# io.net
KiCad netlist of a schematic drawn in Altium Designer
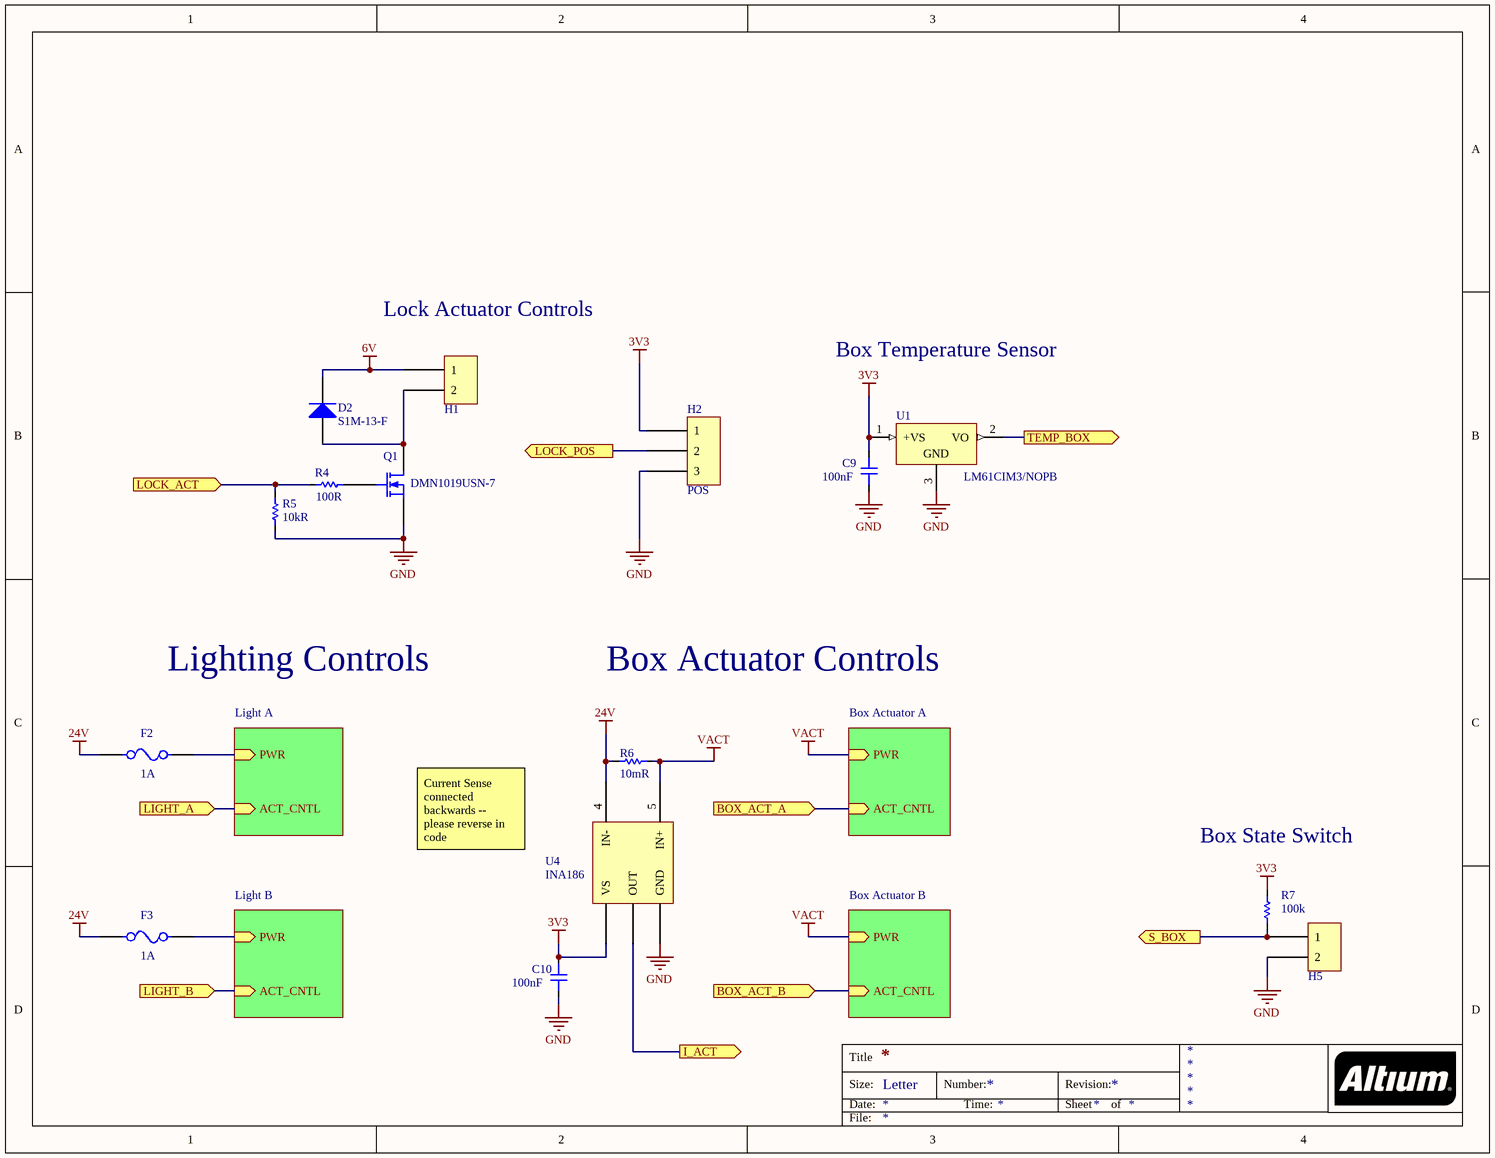
[diagram p0: io.schdoc]

(export (version "E")
  (design (tool "Eeschema 10.0.6"))
  (components
    (comp (ref "C9")
      (value "value")
      (footprint "CAP 0805 L")
      (fields
        (field (name "MANUFACTURER") "KEMET")
        (field (name "MANUFACTURER PART NUMBER") "C0805C104K3RACAUTO")
        (field (name "TOLERANCE") "10%")
        (field (name "CAPACITANCE") "100nF")
      )
      (libsource (lib "streetbot") (part "CAP 0805"))
    )
    (comp (ref "C10")
      (value "value")
      (footprint "CAP 0805 L")
      (fields
        (field (name "MANUFACTURER") "KEMET")
        (field (name "MANUFACTURER PART NUMBER") "C0805C104K3RACAUTO")
        (field (name "TOLERANCE") "10%")
        (field (name "CAPACITANCE") "100nF")
      )
      (libsource (lib "streetbot") (part "CAP 0805"))
    )
    (comp (ref "D2")
      (value "S1M-13-F")
      (footprint "SMA")
      (description "Default Diode")
      (libsource (lib "Miscellaneous Devices") (part "Diode"))
    )
    (comp (ref "F2")
      (value "0154001.DRT")
      (footprint "Littelfuse_0154_0")
      (description "LITTELFUSE - 0154001.DRT - FUSE, SMD, 1A, OMNI BLOCK, TIME DELAY")
      (fields (field (name "MANUFACTURER") "Littelfuse") (field (name "CURRENT RATING") "1A"))
      (libsource (lib "food_box") (part "0154005.DRT"))
    )
    (comp (ref "F3")
      (value "0154001.DRT")
      (footprint "Littelfuse_0154_0")
      (description "LITTELFUSE - 0154001.DRT - FUSE, SMD, 1A, OMNI BLOCK, TIME DELAY")
      (fields (field (name "MANUFACTURER") "Littelfuse") (field (name "CURRENT RATING") "1A"))
      (libsource (lib "food_box") (part "0154005.DRT"))
    )
    (comp (ref "H1")
      (value "MOLEX_43650_2")
      (footprint "MOLEX_43650_2")
      (fields (field (name "MANUFACTURER") "Molex") (field (name "MANUFACTURER PART NUMBER") "43650-0227"))
      (libsource (lib "food_box") (part "MOLEX_43650_2"))
    )
    (comp (ref "H2")
      (value "POS")
      (footprint "MOLEX_43650_3")
      (description "Stepper position potentiometer")
      (libsource (lib "food_box") (part "TERM_3P"))
    )
    (comp (ref "H5")
      (value "MOLEX_43650_2")
      (footprint "MOLEX_43650_2")
      (fields (field (name "MANUFACTURER") "Molex") (field (name "MANUFACTURER PART NUMBER") "43650-0227"))
      (libsource (lib "food_box") (part "MOLEX_43650_2"))
    )
    (comp (ref "Q1")
      (value "MOSFET-N")
      (footprint "SOT23-3")
      (description "MOSFET 12V N-Ch Enh FET 2426pF 27.3nC")
      (fields (field (name "MANUFACTURER") "Diodes") (field (name "MANUFACTURER PART NUMBER") "DMN1019USN-7"))
      (libsource (lib "Miscellaneous Devices") (part "MOSFET-N"))
    )
    (comp (ref "R4")
      (value "value")
      (footprint "RES 0603 L")
      (description "CRGCQ 0603 100R 5%")
      (fields
        (field (name "MANUFACTURER") "TE Connectivity")
        (field (name "MANUFACTURER PART NUMBER") "CRGCQ0603J100R")
        (field (name "RESISTANCE") "100R")
      )
      (libsource (lib "streetbot") (part "RES 0603"))
    )
    (comp (ref "R5")
      (value "value")
      (footprint "RES 0603 L")
      (description "TE CONNECTIVITY - CRGCQ0603J10K - RES, 10K, 5%, 0603, THICK FILM")
      (fields
        (field (name "MANUFACTURER") "TE Connectivity")
        (field (name "MANUFACTURER PART NUMBER") "CRGCQ0603J10K")
        (field (name "RESISTANCE") "10kR")
      )
      (libsource (lib "streetbot") (part "RES 0603"))
    )
    (comp (ref "R6")
      (value "10mR")
      (footprint "CAP 0805 L")
      (description "Resistor Thick Film 0.01Ohm 0.5% 0.5W 2-Pin 0805 T/R")
      (fields
        (field (name "MANUFACTURER") "Panasonic")
        (field (name "MANUFACTURER PART NUMBER") "ERJ-6CWDR010V")
      )
      (libsource (lib "streetbot") (part "RES 0603"))
    )
    (comp (ref "R7")
      (value "value")
      (footprint "RES 0603 L")
      (description "CRGCQ 0603 100K 5%")
      (fields
        (field (name "MANUFACTURER") "TE Connectivity")
        (field (name "MANUFACTURER PART NUMBER") "CRGCQ0603J100K")
        (field (name "RESISTANCE") "100k")
      )
      (libsource (lib "streetbot") (part "RES 0603"))
    )
    (comp (ref "U1")
      (value "LM61CIM3/NOPB")
      (footprint "DBZ0003A_L")
      (description "2.7V Temperature Sensor, 3-pin SOT-23, Pb-Free")
      (fields (field (name "MANUFACTURER") "Texas Instruments"))
      (libsource (lib "Altium Content Vault") (part "SEN-TEMP-LM34AH-3"))
    )
    (comp (ref "U4") (value "INA186") (footprint "SOT23-5") (libsource (lib "food_box") (part "INA186")))
  )
  (nets
    (net (code "3") (name "/I_ACT") (class "Default")
      (node (ref "U4") (pin "2") (pinfunction "OUT_2") (pintype "passive"))
    )
    (net (code "6") (name "/LOCK_ACT") (class "Default")
      (node (ref "R4") (pin "2") (pinfunction "2_2") (pintype "passive"))
      (node (ref "R5") (pin "2") (pinfunction "2_2") (pintype "passive"))
    )
    (net (code "7") (name "/LOCK_POS") (class "Default")
      (node (ref "H2") (pin "2") (pinfunction "2_2") (pintype "passive"))
    )
    (net (code "8") (name "/PWR") (class "Default")
      (node (ref "F3") (pin "2") (pinfunction "2_2") (pintype "passive"))
    )
    (net (code "9") (name "/PWR_1") (class "Default")
      (node (ref "F2") (pin "2") (pinfunction "2_2") (pintype "passive"))
    )
    (net (code "10") (name "/S_BOX") (class "Default")
      (node (ref "H5") (pin "1") (pinfunction "1_1") (pintype "passive"))
      (node (ref "R7") (pin "1") (pinfunction "1_1") (pintype "passive"))
    )
    (net (code "11") (name "/TEMP_BOX") (class "Default")
      (node (ref "U1") (pin "2") (pinfunction "VO_2") (pintype "output"))
    )
    (net (code "12") (name "3V3") (class "Default")
      (node (ref "C10") (pin "2") (pinfunction "2_2") (pintype "passive"))
      (node (ref "C9") (pin "2") (pinfunction "2_2") (pintype "passive"))
      (node (ref "H2") (pin "1") (pinfunction "1_1") (pintype "passive"))
      (node (ref "R7") (pin "2") (pinfunction "2_2") (pintype "passive"))
      (node (ref "U1") (pin "1") (pinfunction "+VS_1") (pintype "input"))
      (node (ref "U4") (pin "3") (pinfunction "VS_3") (pintype "passive"))
    )
    (net (code "13") (name "6V") (class "Default")
      (node (ref "D2") (pin "2") (pinfunction "K_2") (pintype "passive"))
      (node (ref "H1") (pin "1") (pinfunction "1_1") (pintype "passive"))
    )
    (net (code "14") (name "24V") (class "Default")
      (node (ref "F2") (pin "1") (pinfunction "1_1") (pintype "passive"))
      (node (ref "F3") (pin "1") (pinfunction "1_1") (pintype "passive"))
      (node (ref "R6") (pin "2") (pinfunction "2_2") (pintype "passive"))
      (node (ref "U4") (pin "4") (pinfunction "IN-_4") (pintype "passive"))
    )
    (net (code "15") (name "GND") (class "Default")
      (node (ref "C10") (pin "1") (pinfunction "1_1") (pintype "passive"))
      (node (ref "C9") (pin "1") (pinfunction "1_1") (pintype "passive"))
      (node (ref "H2") (pin "3") (pinfunction "3_3") (pintype "passive"))
      (node (ref "H5") (pin "2") (pinfunction "2_2") (pintype "passive"))
      (node (ref "Q1") (pin "3") (pinfunction "S_3") (pintype "passive"))
      (node (ref "R5") (pin "1") (pinfunction "1_1") (pintype "passive"))
      (node (ref "U1") (pin "3") (pinfunction "GND_3") (pintype "power_in"))
      (node (ref "U4") (pin "1") (pinfunction "GND_1") (pintype "passive"))
    )
    (net (code "16") (name "Net-(D2-A)") (class "Default")
      (node (ref "D2") (pin "1") (pinfunction "A_1") (pintype "passive"))
      (node (ref "H1") (pin "2") (pinfunction "2_2") (pintype "passive"))
      (node (ref "Q1") (pin "1") (pinfunction "D_1") (pintype "passive"))
    )
    (net (code "17") (name "Net-(Q1-G)") (class "Default")
      (node (ref "Q1") (pin "2") (pinfunction "G_2") (pintype "passive"))
      (node (ref "R4") (pin "1") (pinfunction "1_1") (pintype "passive"))
    )
    (net (code "18") (name "VACT") (class "Default")
      (node (ref "R6") (pin "1") (pinfunction "1_1") (pintype "passive"))
      (node (ref "U4") (pin "5") (pinfunction "IN+_5") (pintype "passive"))
    )
  )
)
